# ClockBase.net
KiCad netlist of a schematic drawn in Altium Designer
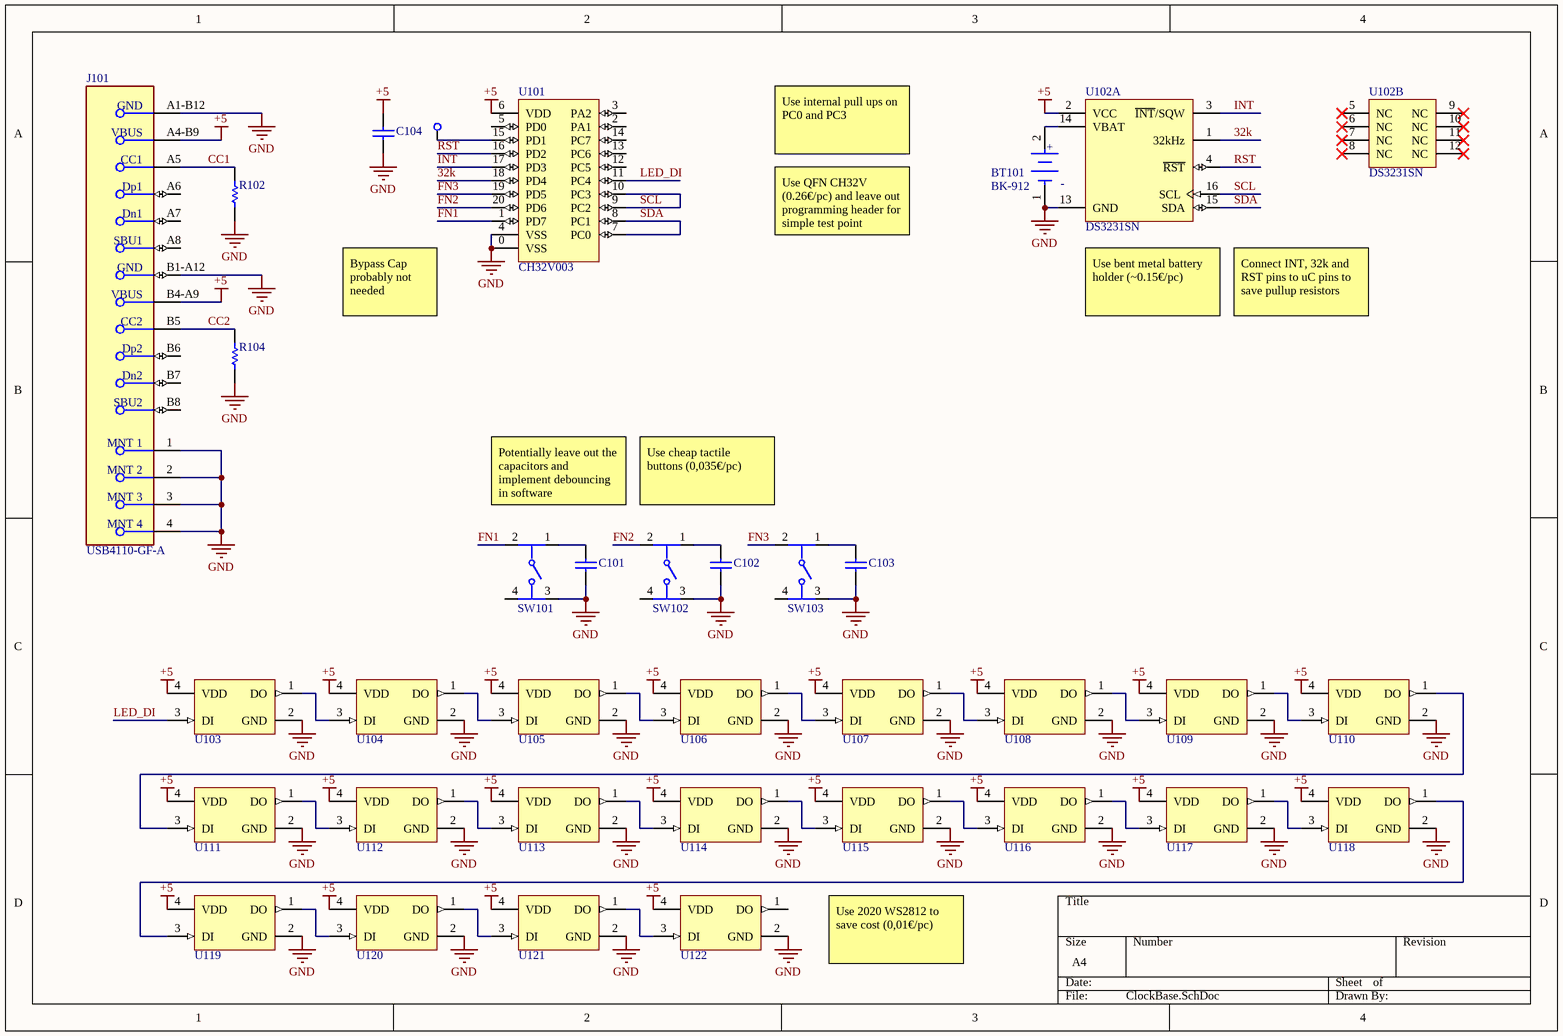
[diagram p0: ClockBase.SchDoc]

(export (version "E")
  (design (tool "Eeschema 10.0.6"))
  (components
    (comp (ref "BT101")
      (value "BK-912")
      (footprint "FP-BK-912-MFG")
      (description "BATTERY RETAINER COIN 20MM SMD")
      (libsource (lib "Altium Content Vault") (part "60d3b5b901a8747834971d0eb8cf3fd"))
    )
    (comp (ref "C101")
      (value "Capacitor")
      (footprint "CAPC1608X09N")
      (libsource (lib "Schlib1") (part "C0603"))
    )
    (comp (ref "C102")
      (value "Capacitor")
      (footprint "CAPC1608X09N")
      (libsource (lib "Schlib1") (part "C0603"))
    )
    (comp (ref "C103")
      (value "Capacitor")
      (footprint "CAPC1608X09N")
      (libsource (lib "Schlib1") (part "C0603"))
    )
    (comp (ref "C104")
      (value "Capacitor")
      (footprint "CAPC1608X09N")
      (libsource (lib "Schlib1") (part "C0603"))
    )
    (comp (ref "J101")
      (value "USB4110-GF-A")
      (footprint "FP-USB4110-GF-A-MFG")
      (description "CONN USB 2.0 TYPE-C R/A SMT")
      (fields
        (field (name "OCTOPART") "https://octopart.com/usb4110-gf-a-gct-103941985")
        (field (name "MANUFACTURER") "GCT")
      )
      (libsource (lib "Altium Content Vault") (part "e23f2b38bb3c3f98e683ebab9ede730"))
    )
    (comp (ref "R102")
      (value "Resistor")
      (footprint "RESC1608X06N")
      (libsource (lib "Schlib1") (part "R0603"))
    )
    (comp (ref "R104")
      (value "Resistor")
      (footprint "RESC1608X06N")
      (libsource (lib "Schlib1") (part "R0603"))
    )
    (comp (ref "SW101")
      (value "PTS526SK15SMTR2LFS")
      (footprint "FP-PTS526SK15SMTR2LFS-MFG")
      (description "TACT 5.2 X 5.2, 1.5 MM H, 260GF,")
      (fields
        (field (name "MANUFACTURER") "C&K")
        (field (name "OCTOPART") "https://octopart.com/pts526+sk15+smtr2+lfs-c%26k+components-100617999")
      )
      (libsource (lib "Altium Content Vault") (part "b8895f3f4cefb76e1819d2863dba89b"))
    )
    (comp (ref "SW102")
      (value "PTS526SK15SMTR2LFS")
      (footprint "FP-PTS526SK15SMTR2LFS-MFG")
      (description "TACT 5.2 X 5.2, 1.5 MM H, 260GF,")
      (fields
        (field (name "MANUFACTURER") "C&K")
        (field (name "OCTOPART") "https://octopart.com/pts526+sk15+smtr2+lfs-c%26k+components-100617999")
      )
      (libsource (lib "Altium Content Vault") (part "b8895f3f4cefb76e1819d2863dba89b"))
    )
    (comp (ref "SW103")
      (value "PTS526SK15SMTR2LFS")
      (footprint "FP-PTS526SK15SMTR2LFS-MFG")
      (description "TACT 5.2 X 5.2, 1.5 MM H, 260GF,")
      (fields
        (field (name "MANUFACTURER") "C&K")
        (field (name "OCTOPART") "https://octopart.com/pts526+sk15+smtr2+lfs-c%26k+components-100617999")
      )
      (libsource (lib "Altium Content Vault") (part "b8895f3f4cefb76e1819d2863dba89b"))
    )
    (comp (ref "TP101")
      (value "TestPoint")
      (footprint "TestPoint")
      (libsource (lib "Schlib1") (part "TestPoint"))
    )
    (comp (ref "U101")
      (value "CH32V003")
      (footprint "QFN40P300X300X75_HS-21N")
      (libsource (lib "Schlib1") (part "CH32V003F4U6"))
    )
    (comp (ref "U102")
      (value "DS3231SN")
      (footprint "SOP127P1030X265-16N")
      (description "Extremely Accurate I2C-Integrated Real-Time Clock/TCXO/Crystal, 16-Pin SO, -40 to 85 degC, Reel")
      (libsource (lib "Schlib1") (part "DS3231SN"))
    )
    (comp (ref "U103")
      (value "NOT COMPATIBLE WITH WS2812B")
      (footprint "LED_WS2812-2020")
      (description "Adressable RGB LED")
      (libsource (lib "Schlib1") (part "WS2812_2018"))
    )
    (comp (ref "U104")
      (value "NOT COMPATIBLE WITH WS2812B")
      (footprint "LED_WS2812-2020")
      (description "Adressable RGB LED")
      (libsource (lib "Schlib1") (part "WS2812_2018"))
    )
    (comp (ref "U105")
      (value "NOT COMPATIBLE WITH WS2812B")
      (footprint "LED_WS2812-2020")
      (description "Adressable RGB LED")
      (libsource (lib "Schlib1") (part "WS2812_2018"))
    )
    (comp (ref "U106")
      (value "NOT COMPATIBLE WITH WS2812B")
      (footprint "LED_WS2812-2020")
      (description "Adressable RGB LED")
      (libsource (lib "Schlib1") (part "WS2812_2018"))
    )
    (comp (ref "U107")
      (value "NOT COMPATIBLE WITH WS2812B")
      (footprint "LED_WS2812-2020")
      (description "Adressable RGB LED")
      (libsource (lib "Schlib1") (part "WS2812_2018"))
    )
    (comp (ref "U108")
      (value "NOT COMPATIBLE WITH WS2812B")
      (footprint "LED_WS2812-2020")
      (description "Adressable RGB LED")
      (libsource (lib "Schlib1") (part "WS2812_2018"))
    )
    (comp (ref "U109")
      (value "NOT COMPATIBLE WITH WS2812B")
      (footprint "LED_WS2812-2020")
      (description "Adressable RGB LED")
      (libsource (lib "Schlib1") (part "WS2812_2018"))
    )
    (comp (ref "U110")
      (value "NOT COMPATIBLE WITH WS2812B")
      (footprint "LED_WS2812-2020")
      (description "Adressable RGB LED")
      (libsource (lib "Schlib1") (part "WS2812_2018"))
    )
    (comp (ref "U111")
      (value "NOT COMPATIBLE WITH WS2812B")
      (footprint "LED_WS2812-2020")
      (description "Adressable RGB LED")
      (libsource (lib "Schlib1") (part "WS2812_2018"))
    )
    (comp (ref "U112")
      (value "NOT COMPATIBLE WITH WS2812B")
      (footprint "LED_WS2812-2020")
      (description "Adressable RGB LED")
      (libsource (lib "Schlib1") (part "WS2812_2018"))
    )
    (comp (ref "U113")
      (value "NOT COMPATIBLE WITH WS2812B")
      (footprint "LED_WS2812-2020")
      (description "Adressable RGB LED")
      (libsource (lib "Schlib1") (part "WS2812_2018"))
    )
    (comp (ref "U114")
      (value "NOT COMPATIBLE WITH WS2812B")
      (footprint "LED_WS2812-2020")
      (description "Adressable RGB LED")
      (libsource (lib "Schlib1") (part "WS2812_2018"))
    )
    (comp (ref "U115")
      (value "NOT COMPATIBLE WITH WS2812B")
      (footprint "LED_WS2812-2020")
      (description "Adressable RGB LED")
      (libsource (lib "Schlib1") (part "WS2812_2018"))
    )
    (comp (ref "U116")
      (value "NOT COMPATIBLE WITH WS2812B")
      (footprint "LED_WS2812-2020")
      (description "Adressable RGB LED")
      (libsource (lib "Schlib1") (part "WS2812_2018"))
    )
    (comp (ref "U117")
      (value "NOT COMPATIBLE WITH WS2812B")
      (footprint "LED_WS2812-2020")
      (description "Adressable RGB LED")
      (libsource (lib "Schlib1") (part "WS2812_2018"))
    )
    (comp (ref "U118")
      (value "NOT COMPATIBLE WITH WS2812B")
      (footprint "LED_WS2812-2020")
      (description "Adressable RGB LED")
      (libsource (lib "Schlib1") (part "WS2812_2018"))
    )
    (comp (ref "U119")
      (value "NOT COMPATIBLE WITH WS2812B")
      (footprint "LED_WS2812-2020")
      (description "Adressable RGB LED")
      (libsource (lib "Schlib1") (part "WS2812_2018"))
    )
    (comp (ref "U120")
      (value "NOT COMPATIBLE WITH WS2812B")
      (footprint "LED_WS2812-2020")
      (description "Adressable RGB LED")
      (libsource (lib "Schlib1") (part "WS2812_2018"))
    )
    (comp (ref "U121")
      (value "NOT COMPATIBLE WITH WS2812B")
      (footprint "LED_WS2812-2020")
      (description "Adressable RGB LED")
      (libsource (lib "Schlib1") (part "WS2812_2018"))
    )
    (comp (ref "U122")
      (value "NOT COMPATIBLE WITH WS2812B")
      (footprint "LED_WS2812-2020")
      (description "Adressable RGB LED")
      (libsource (lib "Schlib1") (part "WS2812_2018"))
    )
  )
  (nets
    (net (code "1") (name "+5") (class "Default")
      (node (ref "C104") (pin "2") (pintype "passive"))
      (node (ref "J101") (pin "A4-B9") (pinfunction "VBUS_A4-B9") (pintype "power_in"))
      (node (ref "J101") (pin "B4-A9") (pinfunction "VBUS_B4-A9") (pintype "power_in"))
      (node (ref "U101") (pin "6") (pinfunction "VDD_6") (pintype "power_in"))
      (node (ref "U102") (pin "2") (pinfunction "VCC_2") (pintype "power_in"))
      (node (ref "U103") (pin "4") (pinfunction "VDD_4") (pintype "power_in"))
      (node (ref "U104") (pin "4") (pinfunction "VDD_4") (pintype "power_in"))
      (node (ref "U105") (pin "4") (pinfunction "VDD_4") (pintype "power_in"))
      (node (ref "U106") (pin "4") (pinfunction "VDD_4") (pintype "power_in"))
      (node (ref "U107") (pin "4") (pinfunction "VDD_4") (pintype "power_in"))
      (node (ref "U108") (pin "4") (pinfunction "VDD_4") (pintype "power_in"))
      (node (ref "U109") (pin "4") (pinfunction "VDD_4") (pintype "power_in"))
      (node (ref "U110") (pin "4") (pinfunction "VDD_4") (pintype "power_in"))
      (node (ref "U111") (pin "4") (pinfunction "VDD_4") (pintype "power_in"))
      (node (ref "U112") (pin "4") (pinfunction "VDD_4") (pintype "power_in"))
      (node (ref "U113") (pin "4") (pinfunction "VDD_4") (pintype "power_in"))
      (node (ref "U114") (pin "4") (pinfunction "VDD_4") (pintype "power_in"))
      (node (ref "U115") (pin "4") (pinfunction "VDD_4") (pintype "power_in"))
      (node (ref "U116") (pin "4") (pinfunction "VDD_4") (pintype "power_in"))
      (node (ref "U117") (pin "4") (pinfunction "VDD_4") (pintype "power_in"))
      (node (ref "U118") (pin "4") (pinfunction "VDD_4") (pintype "power_in"))
      (node (ref "U119") (pin "4") (pinfunction "VDD_4") (pintype "power_in"))
      (node (ref "U120") (pin "4") (pinfunction "VDD_4") (pintype "power_in"))
      (node (ref "U121") (pin "4") (pinfunction "VDD_4") (pintype "power_in"))
      (node (ref "U122") (pin "4") (pinfunction "VDD_4") (pintype "power_in"))
    )
    (net (code "2") (name "/32k") (class "Default")
      (node (ref "U101") (pin "18") (pinfunction "PD4_18") (pintype "bidirectional"))
      (node (ref "U102") (pin "1") (pinfunction "32kHz_1") (pintype "open_collector"))
    )
    (net (code "3") (name "/CC1") (class "Default")
      (node (ref "J101") (pin "A5") (pinfunction "CC1_A5") (pintype "power_in"))
      (node (ref "R102") (pin "2") (pintype "passive"))
    )
    (net (code "4") (name "/CC2") (class "Default")
      (node (ref "J101") (pin "B5") (pinfunction "CC2_B5") (pintype "power_in"))
      (node (ref "R104") (pin "2") (pintype "passive"))
    )
    (net (code "5") (name "/FN1") (class "Default")
      (node (ref "SW101") (pin "2") (pinfunction "2_2") (pintype "passive"))
      (node (ref "U101") (pin "1") (pinfunction "PD7_1") (pintype "bidirectional"))
    )
    (net (code "6") (name "/FN2") (class "Default")
      (node (ref "SW102") (pin "2") (pinfunction "2_2") (pintype "passive"))
      (node (ref "U101") (pin "20") (pinfunction "PD6_20") (pintype "bidirectional"))
    )
    (net (code "7") (name "/FN3") (class "Default")
      (node (ref "SW103") (pin "2") (pinfunction "2_2") (pintype "passive"))
      (node (ref "U101") (pin "19") (pinfunction "PD5_19") (pintype "bidirectional"))
    )
    (net (code "8") (name "/INT") (class "Default")
      (node (ref "U101") (pin "17") (pinfunction "PD3_17") (pintype "bidirectional"))
      (node (ref "U102") (pin "3") (pinfunction "~{INT}/SQW_3") (pintype "open_collector"))
    )
    (net (code "9") (name "/LED_DI") (class "Default")
      (node (ref "U101") (pin "11") (pinfunction "PC4_11") (pintype "bidirectional"))
      (node (ref "U103") (pin "3") (pinfunction "DI_3") (pintype "input"))
    )
    (net (code "10") (name "/RST") (class "Default")
      (node (ref "U101") (pin "16") (pinfunction "PD2_16") (pintype "bidirectional"))
      (node (ref "U102") (pin "4") (pinfunction "~{RST}_4") (pintype "bidirectional"))
    )
    (net (code "11") (name "/SCL") (class "Default")
      (node (ref "U101") (pin "10") (pinfunction "PC3_10") (pintype "bidirectional"))
      (node (ref "U101") (pin "9") (pinfunction "PC2_9") (pintype "bidirectional"))
      (node (ref "U102") (pin "16") (pinfunction "SCL_16") (pintype "input"))
    )
    (net (code "12") (name "/SDA") (class "Default")
      (node (ref "U101") (pin "7") (pinfunction "PC0_7") (pintype "bidirectional"))
      (node (ref "U101") (pin "8") (pinfunction "PC1_8") (pintype "bidirectional"))
      (node (ref "U102") (pin "15") (pinfunction "SDA_15") (pintype "bidirectional"))
    )
    (net (code "13") (name "GND") (class "Default")
      (node (ref "BT101") (pin "1") (pinfunction "C_1") (pintype "passive"))
      (node (ref "C101") (pin "1") (pintype "passive"))
      (node (ref "C102") (pin "1") (pintype "passive"))
      (node (ref "C103") (pin "1") (pintype "passive"))
      (node (ref "C104") (pin "1") (pintype "passive"))
      (node (ref "J101") (pin "1") (pinfunction "MNT_1_1") (pintype "passive"))
      (node (ref "J101") (pin "2") (pinfunction "MNT_2_2") (pintype "passive"))
      (node (ref "J101") (pin "3") (pinfunction "MNT_3_3") (pintype "passive"))
      (node (ref "J101") (pin "4") (pinfunction "MNT_4_4") (pintype "passive"))
      (node (ref "J101") (pin "A1-B12") (pinfunction "GND_A1-B12") (pintype "passive"))
      (node (ref "J101") (pin "B1-A12") (pinfunction "GND_B1-A12") (pintype "bidirectional"))
      (node (ref "R102") (pin "1") (pintype "passive"))
      (node (ref "R104") (pin "1") (pintype "passive"))
      (node (ref "SW101") (pin "3") (pinfunction "3_3") (pintype "passive"))
      (node (ref "SW102") (pin "3") (pinfunction "3_3") (pintype "passive"))
      (node (ref "SW103") (pin "3") (pinfunction "3_3") (pintype "passive"))
      (node (ref "U101") (pin "0") (pinfunction "VSS_0") (pintype "power_in"))
      (node (ref "U101") (pin "4") (pinfunction "VSS_4") (pintype "power_in"))
      (node (ref "U102") (pin "13") (pinfunction "GND_13") (pintype "power_in"))
      (node (ref "U103") (pin "2") (pinfunction "GND_2") (pintype "power_in"))
      (node (ref "U104") (pin "2") (pinfunction "GND_2") (pintype "power_in"))
      (node (ref "U105") (pin "2") (pinfunction "GND_2") (pintype "power_in"))
      (node (ref "U106") (pin "2") (pinfunction "GND_2") (pintype "power_in"))
      (node (ref "U107") (pin "2") (pinfunction "GND_2") (pintype "power_in"))
      (node (ref "U108") (pin "2") (pinfunction "GND_2") (pintype "power_in"))
      (node (ref "U109") (pin "2") (pinfunction "GND_2") (pintype "power_in"))
      (node (ref "U110") (pin "2") (pinfunction "GND_2") (pintype "power_in"))
      (node (ref "U111") (pin "2") (pinfunction "GND_2") (pintype "power_in"))
      (node (ref "U112") (pin "2") (pinfunction "GND_2") (pintype "power_in"))
      (node (ref "U113") (pin "2") (pinfunction "GND_2") (pintype "power_in"))
      (node (ref "U114") (pin "2") (pinfunction "GND_2") (pintype "power_in"))
      (node (ref "U115") (pin "2") (pinfunction "GND_2") (pintype "power_in"))
      (node (ref "U116") (pin "2") (pinfunction "GND_2") (pintype "power_in"))
      (node (ref "U117") (pin "2") (pinfunction "GND_2") (pintype "power_in"))
      (node (ref "U118") (pin "2") (pinfunction "GND_2") (pintype "power_in"))
      (node (ref "U119") (pin "2") (pinfunction "GND_2") (pintype "power_in"))
      (node (ref "U120") (pin "2") (pinfunction "GND_2") (pintype "power_in"))
      (node (ref "U121") (pin "2") (pinfunction "GND_2") (pintype "power_in"))
      (node (ref "U122") (pin "2") (pinfunction "GND_2") (pintype "power_in"))
    )
    (net (code "14") (name "Net-(BT101-A)") (class "Default")
      (node (ref "BT101") (pin "2") (pinfunction "A_2") (pintype "passive"))
      (node (ref "U102") (pin "14") (pinfunction "VBAT_14") (pintype "power_in"))
    )
    (net (code "15") (name "Net-(C101-Pad2)") (class "Default")
      (node (ref "C101") (pin "2") (pintype "passive"))
      (node (ref "SW101") (pin "1") (pinfunction "1_1") (pintype "passive"))
    )
    (net (code "16") (name "Net-(C102-Pad2)") (class "Default")
      (node (ref "C102") (pin "2") (pintype "passive"))
      (node (ref "SW102") (pin "1") (pinfunction "1_1") (pintype "passive"))
    )
    (net (code "17") (name "Net-(C103-Pad2)") (class "Default")
      (node (ref "C103") (pin "2") (pintype "passive"))
      (node (ref "SW103") (pin "1") (pinfunction "1_1") (pintype "passive"))
    )
    (net (code "18") (name "Net-(U101-PD1)") (class "Default")
      (node (ref "TP101") (pin "TP") (pinfunction "TP_TP") (pintype "passive"))
      (node (ref "U101") (pin "15") (pinfunction "PD1_15") (pintype "bidirectional"))
    )
    (net (code "19") (name "Net-(U103-DO)") (class "Default")
      (node (ref "U103") (pin "1") (pinfunction "DO_1") (pintype "output"))
      (node (ref "U104") (pin "3") (pinfunction "DI_3") (pintype "input"))
    )
    (net (code "20") (name "Net-(U104-DO)") (class "Default")
      (node (ref "U104") (pin "1") (pinfunction "DO_1") (pintype "output"))
      (node (ref "U105") (pin "3") (pinfunction "DI_3") (pintype "input"))
    )
    (net (code "21") (name "Net-(U105-DO)") (class "Default")
      (node (ref "U105") (pin "1") (pinfunction "DO_1") (pintype "output"))
      (node (ref "U106") (pin "3") (pinfunction "DI_3") (pintype "input"))
    )
    (net (code "22") (name "Net-(U106-DO)") (class "Default")
      (node (ref "U106") (pin "1") (pinfunction "DO_1") (pintype "output"))
      (node (ref "U107") (pin "3") (pinfunction "DI_3") (pintype "input"))
    )
    (net (code "23") (name "Net-(U107-DO)") (class "Default")
      (node (ref "U107") (pin "1") (pinfunction "DO_1") (pintype "output"))
      (node (ref "U108") (pin "3") (pinfunction "DI_3") (pintype "input"))
    )
    (net (code "24") (name "Net-(U108-DO)") (class "Default")
      (node (ref "U108") (pin "1") (pinfunction "DO_1") (pintype "output"))
      (node (ref "U109") (pin "3") (pinfunction "DI_3") (pintype "input"))
    )
    (net (code "25") (name "Net-(U109-DO)") (class "Default")
      (node (ref "U109") (pin "1") (pinfunction "DO_1") (pintype "output"))
      (node (ref "U110") (pin "3") (pinfunction "DI_3") (pintype "input"))
    )
    (net (code "26") (name "Net-(U110-DO)") (class "Default")
      (node (ref "U110") (pin "1") (pinfunction "DO_1") (pintype "output"))
      (node (ref "U111") (pin "3") (pinfunction "DI_3") (pintype "input"))
    )
    (net (code "27") (name "Net-(U111-DO)") (class "Default")
      (node (ref "U111") (pin "1") (pinfunction "DO_1") (pintype "output"))
      (node (ref "U112") (pin "3") (pinfunction "DI_3") (pintype "input"))
    )
    (net (code "28") (name "Net-(U112-DO)") (class "Default")
      (node (ref "U112") (pin "1") (pinfunction "DO_1") (pintype "output"))
      (node (ref "U113") (pin "3") (pinfunction "DI_3") (pintype "input"))
    )
    (net (code "29") (name "Net-(U113-DO)") (class "Default")
      (node (ref "U113") (pin "1") (pinfunction "DO_1") (pintype "output"))
      (node (ref "U114") (pin "3") (pinfunction "DI_3") (pintype "input"))
    )
    (net (code "30") (name "Net-(U114-DO)") (class "Default")
      (node (ref "U114") (pin "1") (pinfunction "DO_1") (pintype "output"))
      (node (ref "U115") (pin "3") (pinfunction "DI_3") (pintype "input"))
    )
    (net (code "31") (name "Net-(U115-DO)") (class "Default")
      (node (ref "U115") (pin "1") (pinfunction "DO_1") (pintype "output"))
      (node (ref "U116") (pin "3") (pinfunction "DI_3") (pintype "input"))
    )
    (net (code "32") (name "Net-(U116-DO)") (class "Default")
      (node (ref "U116") (pin "1") (pinfunction "DO_1") (pintype "output"))
      (node (ref "U117") (pin "3") (pinfunction "DI_3") (pintype "input"))
    )
    (net (code "33") (name "Net-(U117-DO)") (class "Default")
      (node (ref "U117") (pin "1") (pinfunction "DO_1") (pintype "output"))
      (node (ref "U118") (pin "3") (pinfunction "DI_3") (pintype "input"))
    )
    (net (code "34") (name "Net-(U118-DO)") (class "Default")
      (node (ref "U118") (pin "1") (pinfunction "DO_1") (pintype "output"))
      (node (ref "U119") (pin "3") (pinfunction "DI_3") (pintype "input"))
    )
    (net (code "35") (name "Net-(U119-DO)") (class "Default")
      (node (ref "U119") (pin "1") (pinfunction "DO_1") (pintype "output"))
      (node (ref "U120") (pin "3") (pinfunction "DI_3") (pintype "input"))
    )
    (net (code "36") (name "Net-(U120-DO)") (class "Default")
      (node (ref "U120") (pin "1") (pinfunction "DO_1") (pintype "output"))
      (node (ref "U121") (pin "3") (pinfunction "DI_3") (pintype "input"))
    )
    (net (code "37") (name "Net-(U121-DO)") (class "Default")
      (node (ref "U121") (pin "1") (pinfunction "DO_1") (pintype "output"))
      (node (ref "U122") (pin "3") (pinfunction "DI_3") (pintype "input"))
    )
    (net (code "38") (name "unconnected-(J101-Dn1-PadA7)") (class "Default")
      (node (ref "J101") (pin "A7") (pinfunction "Dn1_A7") (pintype "bidirectional"))
    )
    (net (code "39") (name "unconnected-(J101-Dn2-PadB7)") (class "Default")
      (node (ref "J101") (pin "B7") (pinfunction "Dn2_B7") (pintype "bidirectional"))
    )
    (net (code "40") (name "unconnected-(J101-Dp1-PadA6)") (class "Default")
      (node (ref "J101") (pin "A6") (pinfunction "Dp1_A6") (pintype "bidirectional"))
    )
    (net (code "41") (name "unconnected-(J101-Dp2-PadB6)") (class "Default")
      (node (ref "J101") (pin "B6") (pinfunction "Dp2_B6") (pintype "bidirectional"))
    )
    (net (code "42") (name "unconnected-(J101-SBU1-PadA8)") (class "Default")
      (node (ref "J101") (pin "A8") (pinfunction "SBU1_A8") (pintype "bidirectional"))
    )
    (net (code "43") (name "unconnected-(J101-SBU2-PadB8)") (class "Default")
      (node (ref "J101") (pin "B8") (pinfunction "SBU2_B8") (pintype "bidirectional"))
    )
    (net (code "44") (name "unconnected-(SW101-Pad4)") (class "Default")
      (node (ref "SW101") (pin "4") (pinfunction "4_4") (pintype "passive"))
    )
    (net (code "45") (name "unconnected-(SW102-Pad4)") (class "Default")
      (node (ref "SW102") (pin "4") (pinfunction "4_4") (pintype "passive"))
    )
    (net (code "46") (name "unconnected-(SW103-Pad4)") (class "Default")
      (node (ref "SW103") (pin "4") (pinfunction "4_4") (pintype "passive"))
    )
    (net (code "47") (name "unconnected-(U101-PA1-Pad2)") (class "Default")
      (node (ref "U101") (pin "2") (pinfunction "PA1_2") (pintype "bidirectional"))
    )
    (net (code "48") (name "unconnected-(U101-PA2-Pad3)") (class "Default")
      (node (ref "U101") (pin "3") (pinfunction "PA2_3") (pintype "bidirectional"))
    )
    (net (code "49") (name "unconnected-(U101-PC5-Pad12)") (class "Default")
      (node (ref "U101") (pin "12") (pinfunction "PC5_12") (pintype "bidirectional"))
    )
    (net (code "50") (name "unconnected-(U101-PC6-Pad13)") (class "Default")
      (node (ref "U101") (pin "13") (pinfunction "PC6_13") (pintype "bidirectional"))
    )
    (net (code "51") (name "unconnected-(U101-PC7-Pad14)") (class "Default")
      (node (ref "U101") (pin "14") (pinfunction "PC7_14") (pintype "bidirectional"))
    )
    (net (code "52") (name "unconnected-(U101-PD0-Pad5)") (class "Default")
      (node (ref "U101") (pin "5") (pinfunction "PD0_5") (pintype "bidirectional"))
    )
    (net (code "53") (name "unconnected-(U102B-NC-Pad5)") (class "Default")
      (node (ref "U102") (pin "5") (pinfunction "NC_5") (pintype "passive+no_connect"))
    )
    (net (code "54") (name "unconnected-(U102B-NC-Pad6)") (class "Default")
      (node (ref "U102") (pin "6") (pinfunction "NC_6") (pintype "passive+no_connect"))
    )
    (net (code "55") (name "unconnected-(U102B-NC-Pad7)") (class "Default")
      (node (ref "U102") (pin "7") (pinfunction "NC_7") (pintype "passive+no_connect"))
    )
    (net (code "56") (name "unconnected-(U102B-NC-Pad8)") (class "Default")
      (node (ref "U102") (pin "8") (pinfunction "NC_8") (pintype "passive+no_connect"))
    )
    (net (code "57") (name "unconnected-(U102B-NC-Pad9)") (class "Default")
      (node (ref "U102") (pin "9") (pinfunction "NC_9") (pintype "passive+no_connect"))
    )
    (net (code "58") (name "unconnected-(U102B-NC-Pad10)") (class "Default")
      (node (ref "U102") (pin "10") (pinfunction "NC_10") (pintype "passive+no_connect"))
    )
    (net (code "59") (name "unconnected-(U102B-NC-Pad11)") (class "Default")
      (node (ref "U102") (pin "11") (pinfunction "NC_11") (pintype "passive+no_connect"))
    )
    (net (code "60") (name "unconnected-(U102B-NC-Pad12)") (class "Default")
      (node (ref "U102") (pin "12") (pinfunction "NC_12") (pintype "passive+no_connect"))
    )
    (net (code "61") (name "unconnected-(U122-DO-Pad1)") (class "Default")
      (node (ref "U122") (pin "1") (pinfunction "DO_1") (pintype "output"))
    )
  )
)
